# Promini_GSM.net
KiCad netlist of a schematic drawn in EAGLE
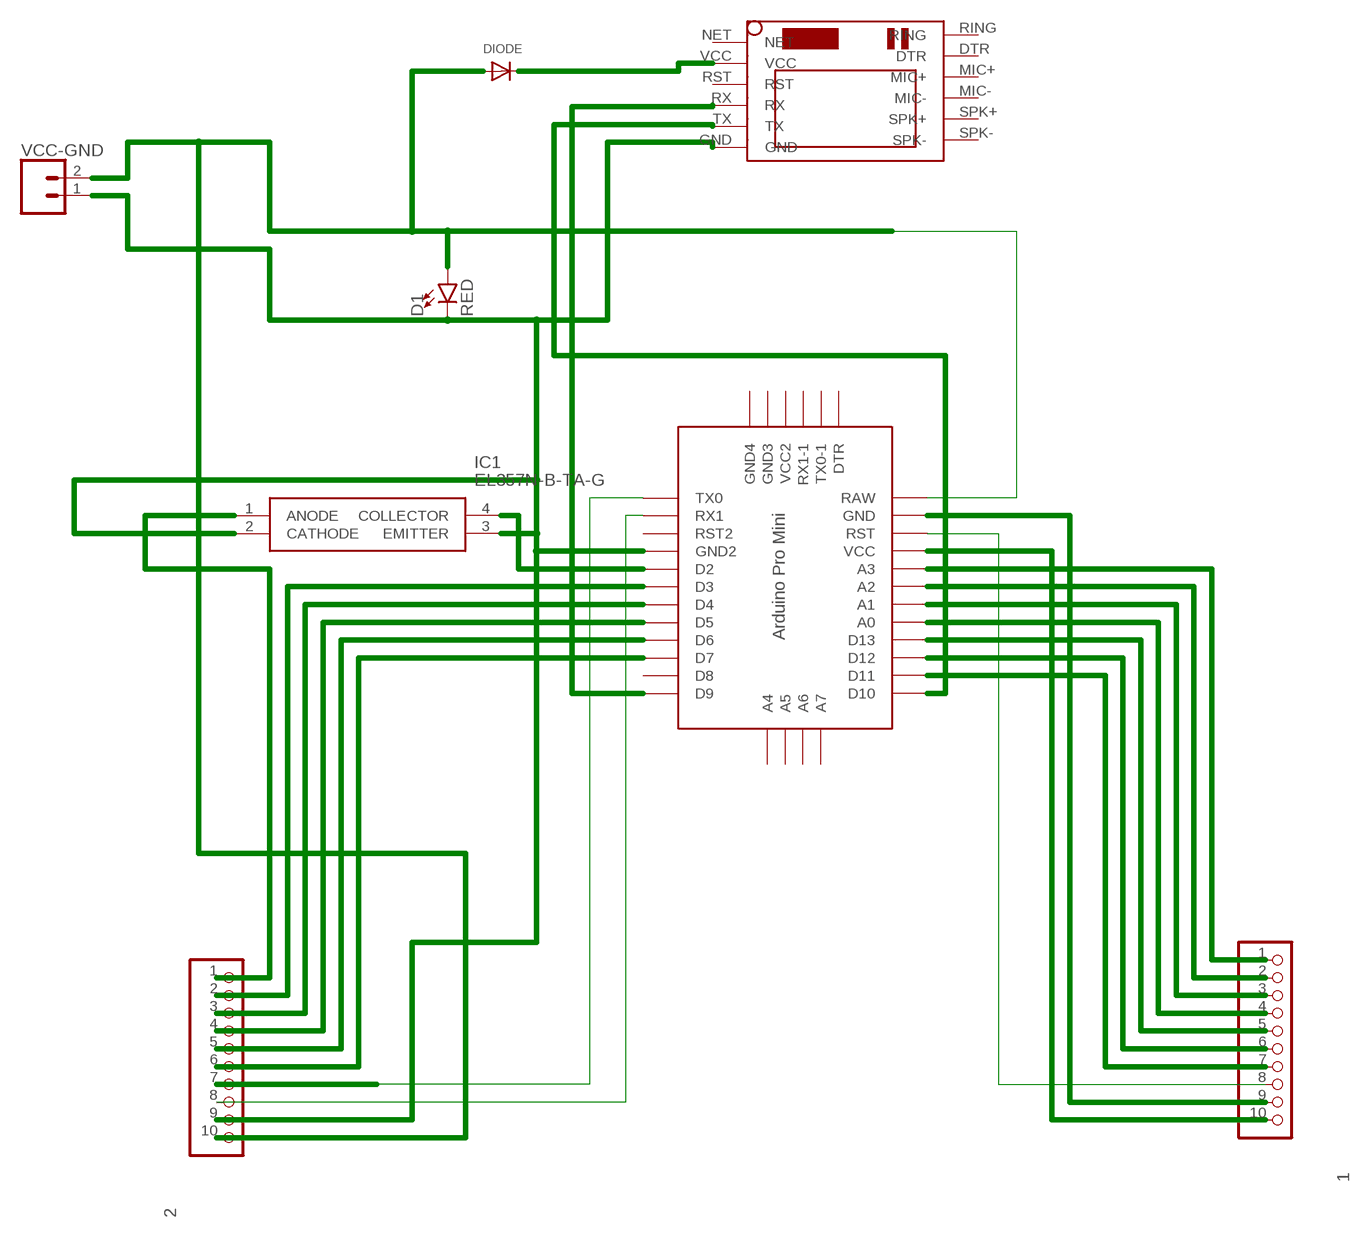
[diagram p0: schematic, sheet 2]

(export (version "E")
  (design (tool "Eeschema 10.0.6"))
  (components
    (comp (ref "1")
      (value "PINHD-1X10")
      (footprint "eagle-import:1X10")
      (libsource (lib "eagle-import") (part "PINHD-1X10"))
    )
    (comp (ref "2")
      (value "PINHD-1X10")
      (footprint "eagle-import:1X10")
      (libsource (lib "eagle-import") (part "PINHD-1X10"))
    )
    (comp (ref "D1")
      (value "RED")
      (footprint "eagle-import:LED-1206")
      (libsource (lib "eagle-import") (part "LED-RED1206"))
    )
    (comp (ref "DIODE")
      (value "DIODESOD-323F")
      (footprint "eagle-import:SOD-323F")
      (libsource (lib "eagle-import") (part "DIODESOD-323F"))
    )
    (comp (ref "IC1")
      (value "EL357N-B-TA-G")
      (footprint "eagle-import:SOP254P700X200-4N")
      (libsource (lib "eagle-import") (part "EL357N-B-TA-G"))
    )
    (comp (ref "PROMINI")
      (value "PRO-MINI")
      (footprint "eagle-import:PRO-MINI")
      (libsource (lib "eagle-import") (part "PRO-MINI"))
    )
    (comp (ref "U$1")
      (value "SIM800LMODULE")
      (footprint "eagle-import:SIM800LMODULE")
      (libsource (lib "eagle-import") (part "SIM800LMODULE"))
    )
    (comp (ref "VCC-GND")
      (value "CONN_025MM")
      (footprint "eagle-import:SCREWTERMINAL-5MM-2")
      (libsource (lib "eagle-import") (part "CONN_025MM"))
    )
  )
  (nets
    (net (code "1") (name "Net-(1-Pad1)") (class "Default")
      (node (ref "1") (pin "1") (pinfunction "1_1") (pintype "passive"))
      (node (ref "PROMINI") (pin "A3") (pinfunction "A3_A3") (pintype "bidirectional"))
    )
    (net (code "2") (name "Net-(1-Pad2)") (class "Default")
      (node (ref "1") (pin "2") (pinfunction "2_2") (pintype "passive"))
      (node (ref "PROMINI") (pin "A2") (pinfunction "A2_A2") (pintype "bidirectional"))
    )
    (net (code "3") (name "Net-(1-Pad3)") (class "Default")
      (node (ref "1") (pin "3") (pinfunction "3_3") (pintype "passive"))
      (node (ref "PROMINI") (pin "A1") (pinfunction "A1_A1") (pintype "bidirectional"))
    )
    (net (code "4") (name "Net-(1-Pad4)") (class "Default")
      (node (ref "1") (pin "4") (pinfunction "4_4") (pintype "passive"))
      (node (ref "PROMINI") (pin "A0") (pinfunction "A0_A0") (pintype "bidirectional"))
    )
    (net (code "5") (name "Net-(1-Pad5)") (class "Default")
      (node (ref "1") (pin "5") (pinfunction "5_5") (pintype "passive"))
      (node (ref "PROMINI") (pin "D13") (pinfunction "D13_D13") (pintype "bidirectional"))
    )
    (net (code "6") (name "Net-(1-Pad6)") (class "Default")
      (node (ref "1") (pin "6") (pinfunction "6_6") (pintype "passive"))
      (node (ref "PROMINI") (pin "D12") (pinfunction "D12_D12") (pintype "bidirectional"))
    )
    (net (code "7") (name "Net-(1-Pad7)") (class "Default")
      (node (ref "1") (pin "7") (pinfunction "7_7") (pintype "passive"))
      (node (ref "PROMINI") (pin "D11") (pinfunction "D11_D11") (pintype "bidirectional"))
    )
    (net (code "8") (name "Net-(1-Pad8)") (class "Default")
      (node (ref "1") (pin "8") (pinfunction "8_8") (pintype "passive"))
      (node (ref "PROMINI") (pin "RST") (pinfunction "RST_RST") (pintype "bidirectional"))
    )
    (net (code "9") (name "Net-(1-Pad9)") (class "Default")
      (node (ref "1") (pin "9") (pinfunction "9_9") (pintype "passive"))
      (node (ref "PROMINI") (pin "GND") (pinfunction "GND_GND") (pintype "input"))
    )
    (net (code "10") (name "Net-(1-Pad10)") (class "Default")
      (node (ref "1") (pin "10") (pinfunction "10_10") (pintype "passive"))
      (node (ref "PROMINI") (pin "VCC") (pinfunction "VCC_VCC") (pintype "bidirectional"))
    )
    (net (code "11") (name "Net-(2-Pad2)") (class "Default")
      (node (ref "2") (pin "2") (pinfunction "2_2") (pintype "passive"))
      (node (ref "PROMINI") (pin "D3") (pinfunction "D3_D3") (pintype "bidirectional"))
    )
    (net (code "12") (name "Net-(2-Pad3)") (class "Default")
      (node (ref "2") (pin "3") (pinfunction "3_3") (pintype "passive"))
      (node (ref "PROMINI") (pin "D4") (pinfunction "D4_D4") (pintype "bidirectional"))
    )
    (net (code "13") (name "Net-(2-Pad4)") (class "Default")
      (node (ref "2") (pin "4") (pinfunction "4_4") (pintype "passive"))
      (node (ref "PROMINI") (pin "D5") (pinfunction "D5_D5") (pintype "bidirectional"))
    )
    (net (code "14") (name "Net-(2-Pad5)") (class "Default")
      (node (ref "2") (pin "5") (pinfunction "5_5") (pintype "passive"))
      (node (ref "PROMINI") (pin "D6") (pinfunction "D6_D6") (pintype "bidirectional"))
    )
    (net (code "15") (name "Net-(2-Pad6)") (class "Default")
      (node (ref "2") (pin "6") (pinfunction "6_6") (pintype "passive"))
      (node (ref "PROMINI") (pin "D7") (pinfunction "D7_D7") (pintype "bidirectional"))
    )
    (net (code "16") (name "Net-(2-Pad7)") (class "Default")
      (node (ref "2") (pin "7") (pinfunction "7_7") (pintype "passive"))
      (node (ref "PROMINI") (pin "TX0") (pinfunction "TX0_TX0") (pintype "bidirectional"))
    )
    (net (code "17") (name "Net-(2-Pad8)") (class "Default")
      (node (ref "2") (pin "8") (pinfunction "8_8") (pintype "passive"))
      (node (ref "PROMINI") (pin "RX1") (pinfunction "RX1_RX1") (pintype "bidirectional"))
    )
    (net (code "18") (name "Net-(2-Pad10)") (class "Default")
      (node (ref "2") (pin "10") (pinfunction "10_10") (pintype "passive"))
      (node (ref "D1") (pin "A") (pinfunction "A_A") (pintype "passive"))
      (node (ref "DIODE") (pin "A") (pinfunction "A_A") (pintype "passive"))
      (node (ref "PROMINI") (pin "RAW") (pinfunction "RAW_RAW") (pintype "power_in"))
      (node (ref "VCC-GND") (pin "2") (pinfunction "2_2") (pintype "passive"))
    )
    (net (code "19") (name "Net-(DIODE-PadC)") (class "Default")
      (node (ref "DIODE") (pin "C") (pinfunction "C_C") (pintype "passive"))
      (node (ref "U$1") (pin "VCC") (pinfunction "VCC_VCC") (pintype "bidirectional"))
    )
    (net (code "20") (name "Net-(IC1-ANODE)") (class "Default")
      (node (ref "2") (pin "1") (pinfunction "1_1") (pintype "passive"))
      (node (ref "IC1") (pin "1") (pinfunction "ANODE_1") (pintype "bidirectional"))
    )
    (net (code "21") (name "Net-(IC1-CATHODE)") (class "Default")
      (node (ref "2") (pin "9") (pinfunction "9_9") (pintype "passive"))
      (node (ref "D1") (pin "C") (pinfunction "C_C") (pintype "passive"))
      (node (ref "IC1") (pin "2") (pinfunction "CATHODE_2") (pintype "bidirectional"))
      (node (ref "IC1") (pin "3") (pinfunction "EMITTER_3") (pintype "bidirectional"))
      (node (ref "PROMINI") (pin "GND1") (pinfunction "GND2_GND1") (pintype "bidirectional"))
      (node (ref "U$1") (pin "GND") (pinfunction "GND_GND") (pintype "bidirectional"))
      (node (ref "VCC-GND") (pin "1") (pinfunction "1_1") (pintype "passive"))
    )
    (net (code "22") (name "Net-(IC1-COLLECTOR)") (class "Default")
      (node (ref "IC1") (pin "4") (pinfunction "COLLECTOR_4") (pintype "bidirectional"))
      (node (ref "PROMINI") (pin "D2") (pinfunction "D2_D2") (pintype "bidirectional"))
    )
    (net (code "23") (name "Net-(PROMINI-PadD9)") (class "Default")
      (node (ref "PROMINI") (pin "D9") (pinfunction "D9_D9") (pintype "bidirectional"))
      (node (ref "U$1") (pin "RX") (pinfunction "RX_RX") (pintype "bidirectional"))
    )
    (net (code "24") (name "Net-(PROMINI-PadD10)") (class "Default")
      (node (ref "PROMINI") (pin "D10") (pinfunction "D10_D10") (pintype "bidirectional"))
      (node (ref "U$1") (pin "TX") (pinfunction "TX_TX") (pintype "bidirectional"))
    )
    (net (code "25") (name "unconnected-(PROMINI-GND4-PadGND2)") (class "Default")
      (node (ref "PROMINI") (pin "GND2") (pinfunction "GND4_GND2") (pintype "bidirectional"))
    )
    (net (code "26") (name "unconnected-(PROMINI-PadA4)") (class "Default")
      (node (ref "PROMINI") (pin "A4") (pinfunction "A4_A4") (pintype "bidirectional"))
    )
    (net (code "27") (name "unconnected-(PROMINI-PadA5)") (class "Default")
      (node (ref "PROMINI") (pin "A5") (pinfunction "A5_A5") (pintype "bidirectional"))
    )
    (net (code "28") (name "unconnected-(PROMINI-PadA6)") (class "Default")
      (node (ref "PROMINI") (pin "A6") (pinfunction "A6_A6") (pintype "bidirectional"))
    )
    (net (code "29") (name "unconnected-(PROMINI-PadA7)") (class "Default")
      (node (ref "PROMINI") (pin "A7") (pinfunction "A7_A7") (pintype "bidirectional"))
    )
    (net (code "30") (name "unconnected-(PROMINI-PadD8)") (class "Default")
      (node (ref "PROMINI") (pin "D8") (pinfunction "D8_D8") (pintype "bidirectional"))
    )
    (net (code "31") (name "unconnected-(PROMINI-PadDTR)") (class "Default")
      (node (ref "PROMINI") (pin "DTR") (pinfunction "DTR_DTR") (pintype "bidirectional"))
    )
    (net (code "32") (name "unconnected-(PROMINI-PadGND3)") (class "Default")
      (node (ref "PROMINI") (pin "GND3") (pinfunction "GND3_GND3") (pintype "bidirectional"))
    )
    (net (code "33") (name "unconnected-(PROMINI-PadRX1-1)") (class "Default")
      (node (ref "PROMINI") (pin "RX1-1") (pinfunction "RX1-1_RX1-1") (pintype "bidirectional"))
    )
    (net (code "34") (name "unconnected-(PROMINI-PadTX0-1)") (class "Default")
      (node (ref "PROMINI") (pin "TX0-1") (pinfunction "TX0-1_TX0-1") (pintype "bidirectional"))
    )
    (net (code "35") (name "unconnected-(PROMINI-RST2-PadRST1)") (class "Default")
      (node (ref "PROMINI") (pin "RST1") (pinfunction "RST2_RST1") (pintype "bidirectional"))
    )
    (net (code "36") (name "unconnected-(PROMINI-VCC2-PadVCC1)") (class "Default")
      (node (ref "PROMINI") (pin "VCC1") (pinfunction "VCC2_VCC1") (pintype "bidirectional"))
    )
    (net (code "37") (name "unconnected-(U$1-PadDTR)") (class "Default")
      (node (ref "U$1") (pin "DTR") (pinfunction "DTR_DTR") (pintype "bidirectional"))
    )
    (net (code "38") (name "unconnected-(U$1-PadMIC+)") (class "Default")
      (node (ref "U$1") (pin "MIC+") (pinfunction "MIC+_MIC+") (pintype "bidirectional"))
    )
    (net (code "39") (name "unconnected-(U$1-PadMIC-)") (class "Default")
      (node (ref "U$1") (pin "MIC-") (pinfunction "MIC-_MIC-") (pintype "bidirectional"))
    )
    (net (code "40") (name "unconnected-(U$1-PadNET)") (class "Default")
      (node (ref "U$1") (pin "NET") (pinfunction "NET_NET") (pintype "bidirectional"))
    )
    (net (code "41") (name "unconnected-(U$1-PadRING)") (class "Default")
      (node (ref "U$1") (pin "RING") (pinfunction "RING_RING") (pintype "bidirectional"))
    )
    (net (code "42") (name "unconnected-(U$1-PadRST)") (class "Default")
      (node (ref "U$1") (pin "RST") (pinfunction "RST_RST") (pintype "bidirectional"))
    )
    (net (code "43") (name "unconnected-(U$1-PadSPK+)") (class "Default")
      (node (ref "U$1") (pin "SPK+") (pinfunction "SPK+_SPK+") (pintype "bidirectional"))
    )
    (net (code "44") (name "unconnected-(U$1-PadSPK-)") (class "Default")
      (node (ref "U$1") (pin "SPK-") (pinfunction "SPK-_SPK-") (pintype "bidirectional"))
    )
  )
)
